# PM_Adapter_Pi_Pico_v3.net
KiCad netlist of a schematic drawn in Altium Designer
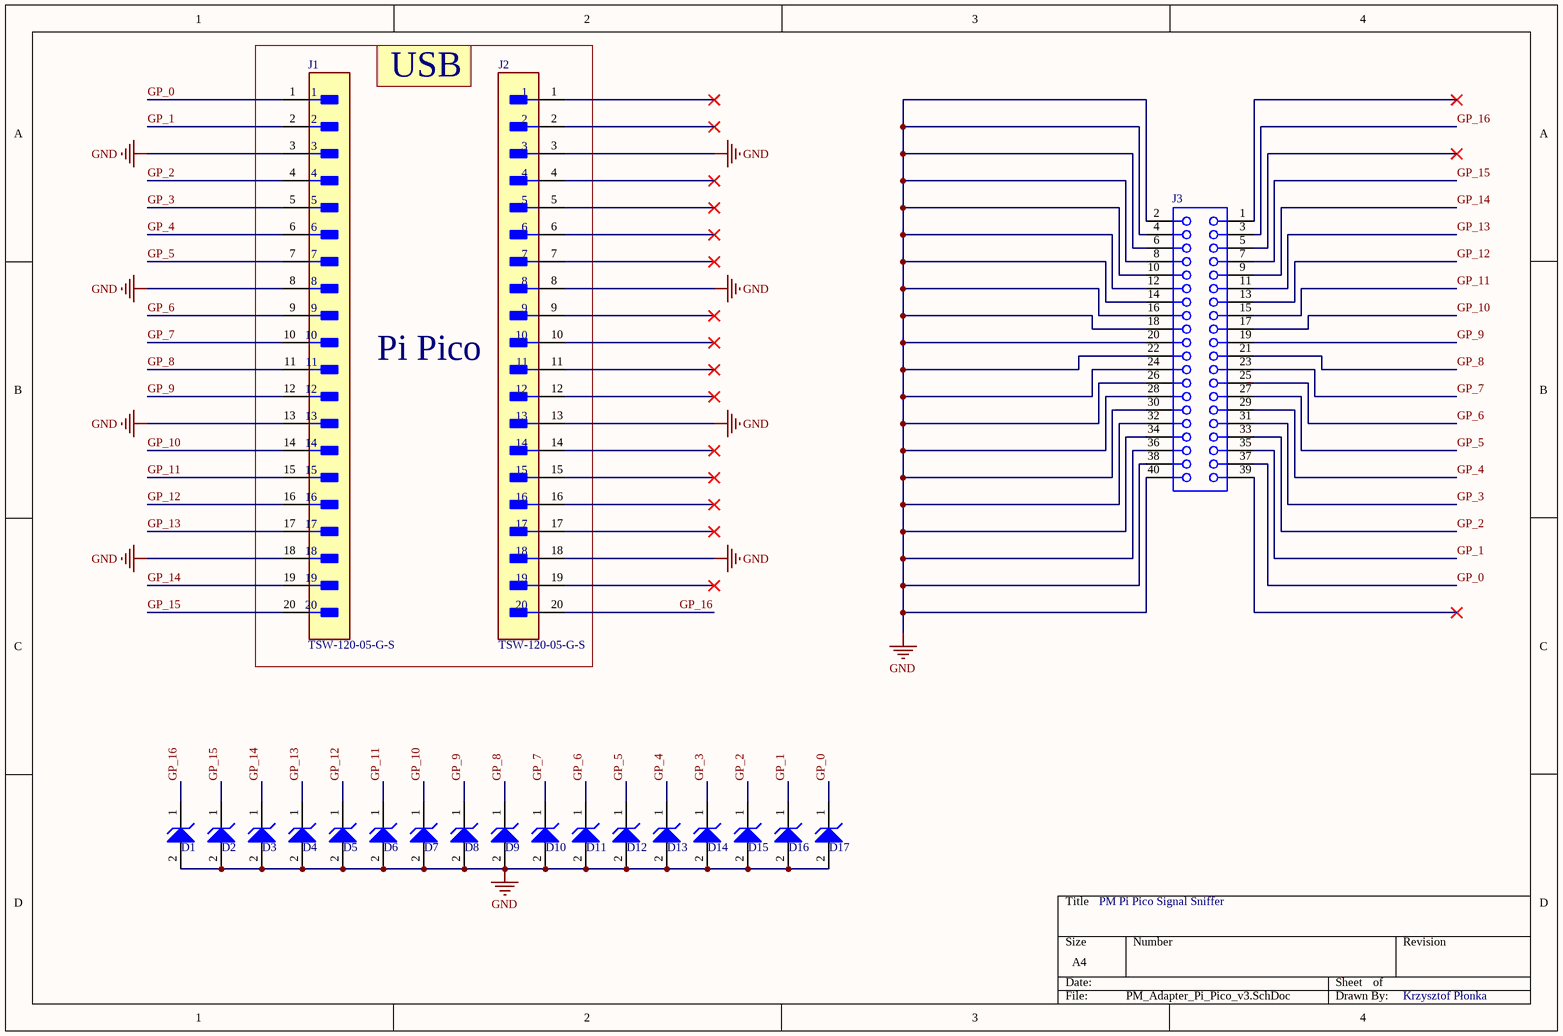
[diagram p0: PM_Adapter_Pi_Pico_v3.SchDoc]

(export (version "E")
  (design (tool "Eeschema 10.0.6"))
  (components
    (comp (ref "D1")
      (value "MM5Z3V6T1G")
      (footprint "ONSC-SOD-523-2-502-01_V")
      (description "Zener Voltage Regulator, 500 mW, 2-Pin SOD-523, Pb-Free, Tape and Reel")
      (fields (field (name "MANUFACTURER") "On Semiconductor"))
      (libsource (lib "Altium Content Vault") (part "ONSC-K1A2-2"))
    )
    (comp (ref "D2")
      (value "MM5Z3V6T1G")
      (footprint "ONSC-SOD-523-2-502-01_V")
      (description "Zener Voltage Regulator, 500 mW, 2-Pin SOD-523, Pb-Free, Tape and Reel")
      (fields (field (name "MANUFACTURER") "On Semiconductor"))
      (libsource (lib "Altium Content Vault") (part "ONSC-K1A2-2"))
    )
    (comp (ref "D3")
      (value "MM5Z3V6T1G")
      (footprint "ONSC-SOD-523-2-502-01_V")
      (description "Zener Voltage Regulator, 500 mW, 2-Pin SOD-523, Pb-Free, Tape and Reel")
      (fields (field (name "MANUFACTURER") "On Semiconductor"))
      (libsource (lib "Altium Content Vault") (part "ONSC-K1A2-2"))
    )
    (comp (ref "D4")
      (value "MM5Z3V6T1G")
      (footprint "ONSC-SOD-523-2-502-01_V")
      (description "Zener Voltage Regulator, 500 mW, 2-Pin SOD-523, Pb-Free, Tape and Reel")
      (fields (field (name "MANUFACTURER") "On Semiconductor"))
      (libsource (lib "Altium Content Vault") (part "ONSC-K1A2-2"))
    )
    (comp (ref "D5")
      (value "MM5Z3V6T1G")
      (footprint "ONSC-SOD-523-2-502-01_V")
      (description "Zener Voltage Regulator, 500 mW, 2-Pin SOD-523, Pb-Free, Tape and Reel")
      (fields (field (name "MANUFACTURER") "On Semiconductor"))
      (libsource (lib "Altium Content Vault") (part "ONSC-K1A2-2"))
    )
    (comp (ref "D6")
      (value "MM5Z3V6T1G")
      (footprint "ONSC-SOD-523-2-502-01_V")
      (description "Zener Voltage Regulator, 500 mW, 2-Pin SOD-523, Pb-Free, Tape and Reel")
      (fields (field (name "MANUFACTURER") "On Semiconductor"))
      (libsource (lib "Altium Content Vault") (part "ONSC-K1A2-2"))
    )
    (comp (ref "D7")
      (value "MM5Z3V6T1G")
      (footprint "ONSC-SOD-523-2-502-01_V")
      (description "Zener Voltage Regulator, 500 mW, 2-Pin SOD-523, Pb-Free, Tape and Reel")
      (fields (field (name "MANUFACTURER") "On Semiconductor"))
      (libsource (lib "Altium Content Vault") (part "ONSC-K1A2-2"))
    )
    (comp (ref "D8")
      (value "MM5Z3V6T1G")
      (footprint "ONSC-SOD-523-2-502-01_V")
      (description "Zener Voltage Regulator, 500 mW, 2-Pin SOD-523, Pb-Free, Tape and Reel")
      (fields (field (name "MANUFACTURER") "On Semiconductor"))
      (libsource (lib "Altium Content Vault") (part "ONSC-K1A2-2"))
    )
    (comp (ref "D9")
      (value "MM5Z3V6T1G")
      (footprint "ONSC-SOD-523-2-502-01_V")
      (description "Zener Voltage Regulator, 500 mW, 2-Pin SOD-523, Pb-Free, Tape and Reel")
      (fields (field (name "MANUFACTURER") "On Semiconductor"))
      (libsource (lib "Altium Content Vault") (part "ONSC-K1A2-2"))
    )
    (comp (ref "D10")
      (value "MM5Z3V6T1G")
      (footprint "ONSC-SOD-523-2-502-01_V")
      (description "Zener Voltage Regulator, 500 mW, 2-Pin SOD-523, Pb-Free, Tape and Reel")
      (fields (field (name "MANUFACTURER") "On Semiconductor"))
      (libsource (lib "Altium Content Vault") (part "ONSC-K1A2-2"))
    )
    (comp (ref "D11")
      (value "MM5Z3V6T1G")
      (footprint "ONSC-SOD-523-2-502-01_V")
      (description "Zener Voltage Regulator, 500 mW, 2-Pin SOD-523, Pb-Free, Tape and Reel")
      (fields (field (name "MANUFACTURER") "On Semiconductor"))
      (libsource (lib "Altium Content Vault") (part "ONSC-K1A2-2"))
    )
    (comp (ref "D12")
      (value "MM5Z3V6T1G")
      (footprint "ONSC-SOD-523-2-502-01_V")
      (description "Zener Voltage Regulator, 500 mW, 2-Pin SOD-523, Pb-Free, Tape and Reel")
      (fields (field (name "MANUFACTURER") "On Semiconductor"))
      (libsource (lib "Altium Content Vault") (part "ONSC-K1A2-2"))
    )
    (comp (ref "D13")
      (value "MM5Z3V6T1G")
      (footprint "ONSC-SOD-523-2-502-01_V")
      (description "Zener Voltage Regulator, 500 mW, 2-Pin SOD-523, Pb-Free, Tape and Reel")
      (fields (field (name "MANUFACTURER") "On Semiconductor"))
      (libsource (lib "Altium Content Vault") (part "ONSC-K1A2-2"))
    )
    (comp (ref "D14")
      (value "MM5Z3V6T1G")
      (footprint "ONSC-SOD-523-2-502-01_V")
      (description "Zener Voltage Regulator, 500 mW, 2-Pin SOD-523, Pb-Free, Tape and Reel")
      (fields (field (name "MANUFACTURER") "On Semiconductor"))
      (libsource (lib "Altium Content Vault") (part "ONSC-K1A2-2"))
    )
    (comp (ref "D15")
      (value "MM5Z3V6T1G")
      (footprint "ONSC-SOD-523-2-502-01_V")
      (description "Zener Voltage Regulator, 500 mW, 2-Pin SOD-523, Pb-Free, Tape and Reel")
      (fields (field (name "MANUFACTURER") "On Semiconductor"))
      (libsource (lib "Altium Content Vault") (part "ONSC-K1A2-2"))
    )
    (comp (ref "D16")
      (value "MM5Z3V6T1G")
      (footprint "ONSC-SOD-523-2-502-01_V")
      (description "Zener Voltage Regulator, 500 mW, 2-Pin SOD-523, Pb-Free, Tape and Reel")
      (fields (field (name "MANUFACTURER") "On Semiconductor"))
      (libsource (lib "Altium Content Vault") (part "ONSC-K1A2-2"))
    )
    (comp (ref "D17")
      (value "MM5Z3V6T1G")
      (footprint "ONSC-SOD-523-2-502-01_V")
      (description "Zener Voltage Regulator, 500 mW, 2-Pin SOD-523, Pb-Free, Tape and Reel")
      (fields (field (name "MANUFACTURER") "On Semiconductor"))
      (libsource (lib "Altium Content Vault") (part "ONSC-K1A2-2"))
    )
    (comp (ref "J1")
      (value "TSW-120-05-G-S")
      (footprint "FP-TSW-120-05-G-S-MFG")
      (description "TSW-120-05-G-S Headers & Wire Housings Classic PCB Header Strips, 0.100 pitch")
      (libsource (lib "Altium Content Vault") (part "aa9a6f52efaac70338c2092749629fc"))
    )
    (comp (ref "J2")
      (value "TSW-120-05-G-S")
      (footprint "FP-TSW-120-05-G-S-MFG")
      (description "TSW-120-05-G-S Headers & Wire Housings Classic PCB Header Strips, 0.100 pitch")
      (libsource (lib "Altium Content Vault") (part "aa9a6f52efaac70338c2092749629fc"))
    )
    (comp (ref "J3")
      (value "SSW-120-02-G-D-RA")
      (footprint "SMTC-SSW-120-02-X-D-RA")
      (description "SQ Post Socket, Through-hole, Right Angle, -55 to 125 degC, 2.54 mm Pitch, 40-Pin, Female, RoHS")
      (fields (field (name "MANUFACTURER") "Samtec"))
      (libsource (lib "Altium Content Vault") (part "SMTC-SSW-120-X-X-D"))
    )
  )
  (nets
    (net (code "1") (name "/GP_0") (class "Default")
      (node (ref "D17") (pin "1") (pinfunction "K_1") (pintype "passive"))
      (node (ref "J1") (pin "1") (pinfunction "1_1") (pintype "passive"))
      (node (ref "J3") (pin "37") (pinfunction "37_37") (pintype "passive"))
    )
    (net (code "2") (name "/GP_1") (class "Default")
      (node (ref "D16") (pin "1") (pinfunction "K_1") (pintype "passive"))
      (node (ref "J1") (pin "2") (pinfunction "2_2") (pintype "passive"))
      (node (ref "J3") (pin "35") (pinfunction "35_35") (pintype "passive"))
    )
    (net (code "3") (name "/GP_2") (class "Default")
      (node (ref "D15") (pin "1") (pinfunction "K_1") (pintype "passive"))
      (node (ref "J1") (pin "4") (pinfunction "4_4") (pintype "passive"))
      (node (ref "J3") (pin "33") (pinfunction "33_33") (pintype "passive"))
    )
    (net (code "4") (name "/GP_3") (class "Default")
      (node (ref "D14") (pin "1") (pinfunction "K_1") (pintype "passive"))
      (node (ref "J1") (pin "5") (pinfunction "5_5") (pintype "passive"))
      (node (ref "J3") (pin "31") (pinfunction "31_31") (pintype "passive"))
    )
    (net (code "5") (name "/GP_4") (class "Default")
      (node (ref "D13") (pin "1") (pinfunction "K_1") (pintype "passive"))
      (node (ref "J1") (pin "6") (pinfunction "6_6") (pintype "passive"))
      (node (ref "J3") (pin "29") (pinfunction "29_29") (pintype "passive"))
    )
    (net (code "6") (name "/GP_5") (class "Default")
      (node (ref "D12") (pin "1") (pinfunction "K_1") (pintype "passive"))
      (node (ref "J1") (pin "7") (pinfunction "7_7") (pintype "passive"))
      (node (ref "J3") (pin "27") (pinfunction "27_27") (pintype "passive"))
    )
    (net (code "7") (name "/GP_6") (class "Default")
      (node (ref "D11") (pin "1") (pinfunction "K_1") (pintype "passive"))
      (node (ref "J1") (pin "9") (pinfunction "9_9") (pintype "passive"))
      (node (ref "J3") (pin "25") (pinfunction "25_25") (pintype "passive"))
    )
    (net (code "8") (name "/GP_7") (class "Default")
      (node (ref "D10") (pin "1") (pinfunction "K_1") (pintype "passive"))
      (node (ref "J1") (pin "10") (pinfunction "10_10") (pintype "passive"))
      (node (ref "J3") (pin "23") (pinfunction "23_23") (pintype "passive"))
    )
    (net (code "9") (name "/GP_8") (class "Default")
      (node (ref "D9") (pin "1") (pinfunction "K_1") (pintype "passive"))
      (node (ref "J1") (pin "11") (pinfunction "11_11") (pintype "passive"))
      (node (ref "J3") (pin "21") (pinfunction "21_21") (pintype "passive"))
    )
    (net (code "10") (name "/GP_9") (class "Default")
      (node (ref "D8") (pin "1") (pinfunction "K_1") (pintype "passive"))
      (node (ref "J1") (pin "12") (pinfunction "12_12") (pintype "passive"))
      (node (ref "J3") (pin "19") (pinfunction "19_19") (pintype "passive"))
    )
    (net (code "11") (name "/GP_10") (class "Default")
      (node (ref "D7") (pin "1") (pinfunction "K_1") (pintype "passive"))
      (node (ref "J1") (pin "14") (pinfunction "14_14") (pintype "passive"))
      (node (ref "J3") (pin "17") (pinfunction "17_17") (pintype "passive"))
    )
    (net (code "12") (name "/GP_11") (class "Default")
      (node (ref "D6") (pin "1") (pinfunction "K_1") (pintype "passive"))
      (node (ref "J1") (pin "15") (pinfunction "15_15") (pintype "passive"))
      (node (ref "J3") (pin "15") (pinfunction "15_15") (pintype "passive"))
    )
    (net (code "13") (name "/GP_12") (class "Default")
      (node (ref "D5") (pin "1") (pinfunction "K_1") (pintype "passive"))
      (node (ref "J1") (pin "16") (pinfunction "16_16") (pintype "passive"))
      (node (ref "J3") (pin "13") (pinfunction "13_13") (pintype "passive"))
    )
    (net (code "14") (name "/GP_13") (class "Default")
      (node (ref "D4") (pin "1") (pinfunction "K_1") (pintype "passive"))
      (node (ref "J1") (pin "17") (pinfunction "17_17") (pintype "passive"))
      (node (ref "J3") (pin "11") (pinfunction "11_11") (pintype "passive"))
    )
    (net (code "15") (name "/GP_14") (class "Default")
      (node (ref "D3") (pin "1") (pinfunction "K_1") (pintype "passive"))
      (node (ref "J1") (pin "19") (pinfunction "19_19") (pintype "passive"))
      (node (ref "J3") (pin "9") (pinfunction "9_9") (pintype "passive"))
    )
    (net (code "16") (name "/GP_15") (class "Default")
      (node (ref "D2") (pin "1") (pinfunction "K_1") (pintype "passive"))
      (node (ref "J1") (pin "20") (pinfunction "20_20") (pintype "passive"))
      (node (ref "J3") (pin "7") (pinfunction "7_7") (pintype "passive"))
    )
    (net (code "17") (name "/GP_16") (class "Default")
      (node (ref "D1") (pin "1") (pinfunction "K_1") (pintype "passive"))
      (node (ref "J2") (pin "20") (pinfunction "20_20") (pintype "passive"))
      (node (ref "J3") (pin "3") (pinfunction "3_3") (pintype "passive"))
    )
    (net (code "18") (name "GND") (class "Default")
      (node (ref "D1") (pin "2") (pinfunction "A_2") (pintype "passive"))
      (node (ref "D10") (pin "2") (pinfunction "A_2") (pintype "passive"))
      (node (ref "D11") (pin "2") (pinfunction "A_2") (pintype "passive"))
      (node (ref "D12") (pin "2") (pinfunction "A_2") (pintype "passive"))
      (node (ref "D13") (pin "2") (pinfunction "A_2") (pintype "passive"))
      (node (ref "D14") (pin "2") (pinfunction "A_2") (pintype "passive"))
      (node (ref "D15") (pin "2") (pinfunction "A_2") (pintype "passive"))
      (node (ref "D16") (pin "2") (pinfunction "A_2") (pintype "passive"))
      (node (ref "D17") (pin "2") (pinfunction "A_2") (pintype "passive"))
      (node (ref "D2") (pin "2") (pinfunction "A_2") (pintype "passive"))
      (node (ref "D3") (pin "2") (pinfunction "A_2") (pintype "passive"))
      (node (ref "D4") (pin "2") (pinfunction "A_2") (pintype "passive"))
      (node (ref "D5") (pin "2") (pinfunction "A_2") (pintype "passive"))
      (node (ref "D6") (pin "2") (pinfunction "A_2") (pintype "passive"))
      (node (ref "D7") (pin "2") (pinfunction "A_2") (pintype "passive"))
      (node (ref "D8") (pin "2") (pinfunction "A_2") (pintype "passive"))
      (node (ref "D9") (pin "2") (pinfunction "A_2") (pintype "passive"))
      (node (ref "J1") (pin "13") (pinfunction "13_13") (pintype "passive"))
      (node (ref "J1") (pin "18") (pinfunction "18_18") (pintype "passive"))
      (node (ref "J1") (pin "3") (pinfunction "3_3") (pintype "passive"))
      (node (ref "J1") (pin "8") (pinfunction "8_8") (pintype "passive"))
      (node (ref "J2") (pin "13") (pinfunction "13_13") (pintype "passive"))
      (node (ref "J2") (pin "18") (pinfunction "18_18") (pintype "passive"))
      (node (ref "J2") (pin "3") (pinfunction "3_3") (pintype "passive"))
      (node (ref "J2") (pin "8") (pinfunction "8_8") (pintype "passive"))
      (node (ref "J3") (pin "10") (pinfunction "10_10") (pintype "passive"))
      (node (ref "J3") (pin "12") (pinfunction "12_12") (pintype "passive"))
      (node (ref "J3") (pin "14") (pinfunction "14_14") (pintype "passive"))
      (node (ref "J3") (pin "16") (pinfunction "16_16") (pintype "passive"))
      (node (ref "J3") (pin "18") (pinfunction "18_18") (pintype "passive"))
      (node (ref "J3") (pin "2") (pinfunction "2_2") (pintype "passive"))
      (node (ref "J3") (pin "20") (pinfunction "20_20") (pintype "passive"))
      (node (ref "J3") (pin "22") (pinfunction "22_22") (pintype "passive"))
      (node (ref "J3") (pin "24") (pinfunction "24_24") (pintype "passive"))
      (node (ref "J3") (pin "26") (pinfunction "26_26") (pintype "passive"))
      (node (ref "J3") (pin "28") (pinfunction "28_28") (pintype "passive"))
      (node (ref "J3") (pin "30") (pinfunction "30_30") (pintype "passive"))
      (node (ref "J3") (pin "32") (pinfunction "32_32") (pintype "passive"))
      (node (ref "J3") (pin "34") (pinfunction "34_34") (pintype "passive"))
      (node (ref "J3") (pin "36") (pinfunction "36_36") (pintype "passive"))
      (node (ref "J3") (pin "38") (pinfunction "38_38") (pintype "passive"))
      (node (ref "J3") (pin "4") (pinfunction "4_4") (pintype "passive"))
      (node (ref "J3") (pin "40") (pinfunction "40_40") (pintype "passive"))
      (node (ref "J3") (pin "6") (pinfunction "6_6") (pintype "passive"))
      (node (ref "J3") (pin "8") (pinfunction "8_8") (pintype "passive"))
    )
    (net (code "19") (name "unconnected-(J2-Pad1)") (class "Default")
      (node (ref "J2") (pin "1") (pinfunction "1_1") (pintype "passive+no_connect"))
    )
    (net (code "20") (name "unconnected-(J2-Pad2)") (class "Default")
      (node (ref "J2") (pin "2") (pinfunction "2_2") (pintype "passive+no_connect"))
    )
    (net (code "21") (name "unconnected-(J2-Pad4)") (class "Default")
      (node (ref "J2") (pin "4") (pinfunction "4_4") (pintype "passive+no_connect"))
    )
    (net (code "22") (name "unconnected-(J2-Pad5)") (class "Default")
      (node (ref "J2") (pin "5") (pinfunction "5_5") (pintype "passive+no_connect"))
    )
    (net (code "23") (name "unconnected-(J2-Pad6)") (class "Default")
      (node (ref "J2") (pin "6") (pinfunction "6_6") (pintype "passive+no_connect"))
    )
    (net (code "24") (name "unconnected-(J2-Pad7)") (class "Default")
      (node (ref "J2") (pin "7") (pinfunction "7_7") (pintype "passive+no_connect"))
    )
    (net (code "25") (name "unconnected-(J2-Pad9)") (class "Default")
      (node (ref "J2") (pin "9") (pinfunction "9_9") (pintype "passive+no_connect"))
    )
    (net (code "26") (name "unconnected-(J2-Pad10)") (class "Default")
      (node (ref "J2") (pin "10") (pinfunction "10_10") (pintype "passive+no_connect"))
    )
    (net (code "27") (name "unconnected-(J2-Pad11)") (class "Default")
      (node (ref "J2") (pin "11") (pinfunction "11_11") (pintype "passive+no_connect"))
    )
    (net (code "28") (name "unconnected-(J2-Pad12)") (class "Default")
      (node (ref "J2") (pin "12") (pinfunction "12_12") (pintype "passive+no_connect"))
    )
    (net (code "29") (name "unconnected-(J2-Pad14)") (class "Default")
      (node (ref "J2") (pin "14") (pinfunction "14_14") (pintype "passive+no_connect"))
    )
    (net (code "30") (name "unconnected-(J2-Pad15)") (class "Default")
      (node (ref "J2") (pin "15") (pinfunction "15_15") (pintype "passive+no_connect"))
    )
    (net (code "31") (name "unconnected-(J2-Pad16)") (class "Default")
      (node (ref "J2") (pin "16") (pinfunction "16_16") (pintype "passive+no_connect"))
    )
    (net (code "32") (name "unconnected-(J2-Pad17)") (class "Default")
      (node (ref "J2") (pin "17") (pinfunction "17_17") (pintype "passive+no_connect"))
    )
    (net (code "33") (name "unconnected-(J2-Pad19)") (class "Default")
      (node (ref "J2") (pin "19") (pinfunction "19_19") (pintype "passive+no_connect"))
    )
    (net (code "34") (name "unconnected-(J3-Pad1)") (class "Default")
      (node (ref "J3") (pin "1") (pinfunction "1_1") (pintype "passive+no_connect"))
    )
    (net (code "35") (name "unconnected-(J3-Pad5)") (class "Default")
      (node (ref "J3") (pin "5") (pinfunction "5_5") (pintype "passive+no_connect"))
    )
    (net (code "36") (name "unconnected-(J3-Pad39)") (class "Default")
      (node (ref "J3") (pin "39") (pinfunction "39_39") (pintype "passive+no_connect"))
    )
  )
)
